# TEMP_HEATER.net
KiCad netlist of a schematic drawn in Altium Designer
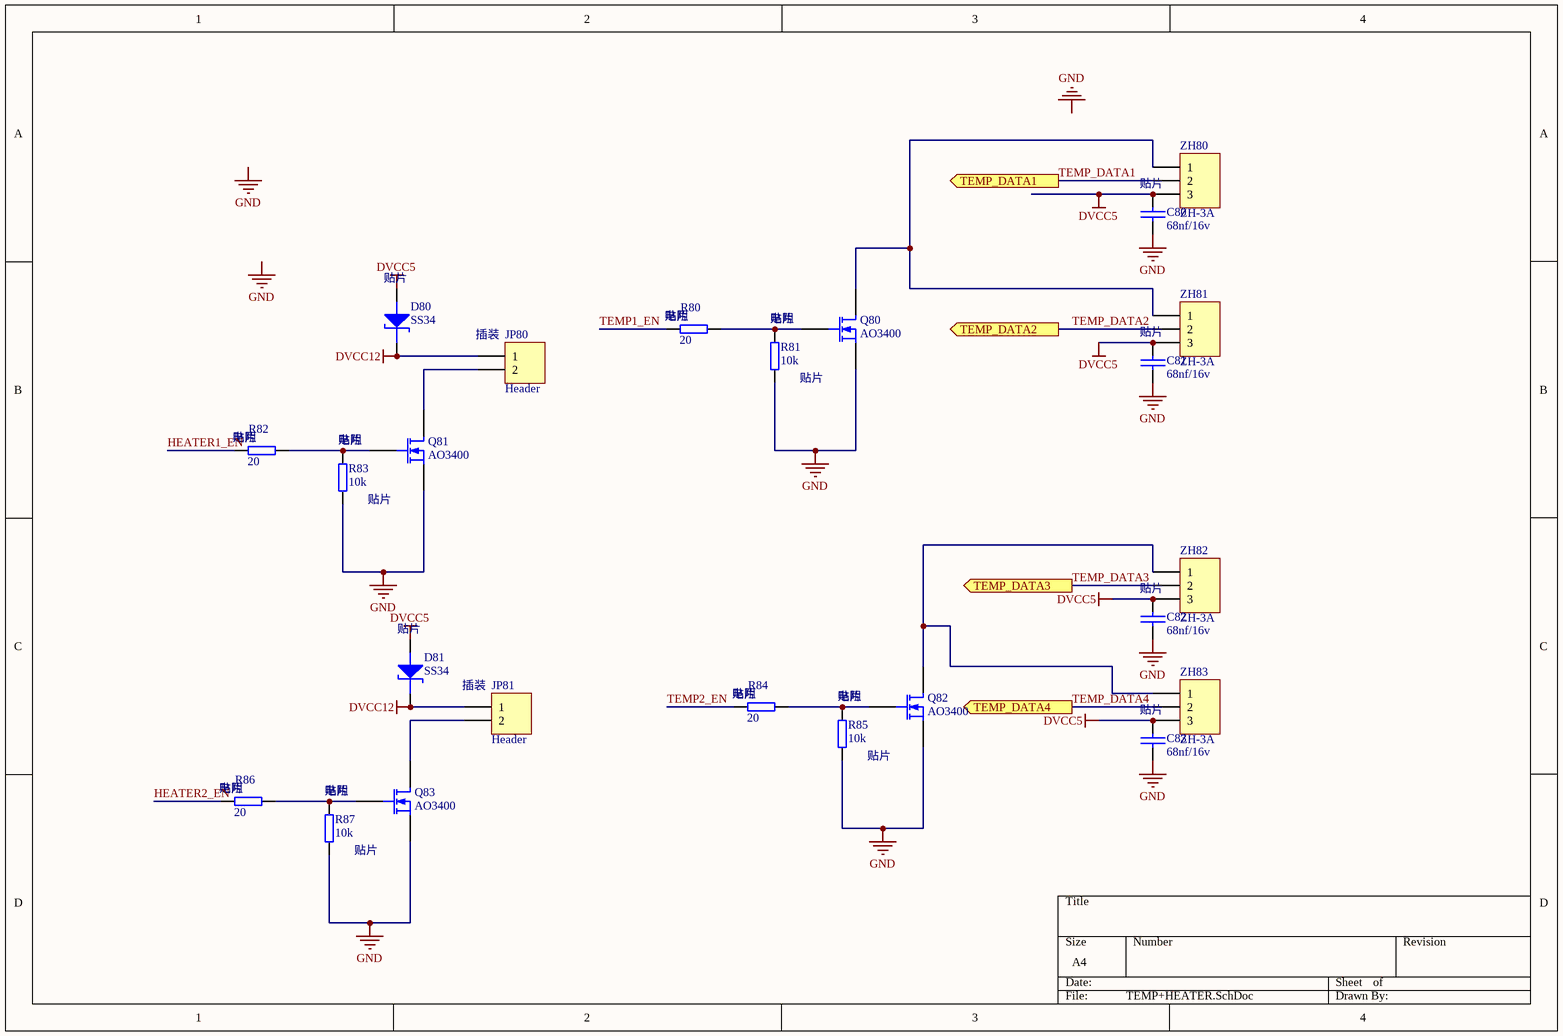
[diagram p0: TEMP+HEATER.SchDoc]

(export (version "E")
  (design (tool "Eeschema 10.0.6"))
  (components
    (comp (ref "C80")
      (value "68nf/16v")
      (footprint "C0402")
      (description "C")
      (libsource (lib "CxyDXP_SCH") (part "CC"))
    )
    (comp (ref "C81")
      (value "68nf/16v")
      (footprint "C0402")
      (description "C")
      (libsource (lib "CxyDXP_SCH") (part "CC"))
    )
    (comp (ref "C82")
      (value "68nf/16v")
      (footprint "C0402")
      (description "C")
      (libsource (lib "CxyDXP_SCH") (part "CC"))
    )
    (comp (ref "C83")
      (value "68nf/16v")
      (footprint "C0402")
      (description "C")
      (libsource (lib "CxyDXP_SCH") (part "CC"))
    )
    (comp (ref "D80") (value "SS34") (footprint "BGY220D") (libsource (lib "CxyDXP_SCH") (part "1N5819")))
    (comp (ref "D81") (value "SS34") (footprint "BGY220D") (libsource (lib "CxyDXP_SCH") (part "1N5819")))
    (comp (ref "JP80")
      (value "Header")
      (footprint "PTC")
      (description "Header, 2-Pin")
      (libsource (lib "Miscellaneous Connectors") (part "Header 2"))
    )
    (comp (ref "JP81")
      (value "Header")
      (footprint "PTC")
      (description "Header, 2-Pin")
      (libsource (lib "Miscellaneous Connectors") (part "Header 2"))
    )
    (comp (ref "Q80")
      (value "AO3400")
      (footprint "SI2300")
      (description "N-Channel MOSFET")
      (libsource (lib "Miscellaneous Devices") (part "MOSFET-N"))
    )
    (comp (ref "Q81")
      (value "AO3400")
      (footprint "SI2300")
      (description "N-Channel MOSFET")
      (libsource (lib "Miscellaneous Devices") (part "MOSFET-N"))
    )
    (comp (ref "Q82")
      (value "AO3400")
      (footprint "SI2300")
      (description "N-Channel MOSFET")
      (libsource (lib "Miscellaneous Devices") (part "MOSFET-N"))
    )
    (comp (ref "Q83")
      (value "AO3400")
      (footprint "SI2300")
      (description "N-Channel MOSFET")
      (libsource (lib "Miscellaneous Devices") (part "MOSFET-N"))
    )
    (comp (ref "R80") (value "20") (footprint "R0402") (libsource (lib "CxyDXP_SCH") (part "RES1")))
    (comp (ref "R81") (value "10k") (footprint "R0402") (libsource (lib "CxyDXP_SCH") (part "RES1")))
    (comp (ref "R82") (value "20") (footprint "R0402") (libsource (lib "CxyDXP_SCH") (part "RES1")))
    (comp (ref "R83") (value "10k") (footprint "R0402") (libsource (lib "CxyDXP_SCH") (part "RES1")))
    (comp (ref "R84") (value "20") (footprint "R0402") (libsource (lib "CxyDXP_SCH") (part "RES1")))
    (comp (ref "R85") (value "10k") (footprint "R0402") (libsource (lib "CxyDXP_SCH") (part "RES1")))
    (comp (ref "R86") (value "20") (footprint "R0402") (libsource (lib "CxyDXP_SCH") (part "RES1")))
    (comp (ref "R87") (value "10k") (footprint "R0402") (libsource (lib "CxyDXP_SCH") (part "RES1")))
    (comp (ref "ZH80")
      (value "ZH-3A")
      (footprint "DS18B20")
      (description "1.5mm")
      (fields (field (name "PUBLISHER") "Altium Limited"))
      (libsource (lib "Connectors") (part "ZH-3A"))
    )
    (comp (ref "ZH81")
      (value "ZH-3A")
      (footprint "DS18B20")
      (description "1.5mm")
      (fields (field (name "PUBLISHER") "Altium Limited"))
      (libsource (lib "Connectors") (part "ZH-3A"))
    )
    (comp (ref "ZH82")
      (value "ZH-3A")
      (footprint "DS18B20")
      (description "1.5mm")
      (fields (field (name "PUBLISHER") "Altium Limited"))
      (libsource (lib "Connectors") (part "ZH-3A"))
    )
    (comp (ref "ZH83")
      (value "ZH-3A")
      (footprint "DS18B20")
      (description "1.5mm")
      (fields (field (name "PUBLISHER") "Altium Limited"))
      (libsource (lib "Connectors") (part "ZH-3A"))
    )
  )
  (nets
    (net (code "1") (name "/HEATER1_EN") (class "Default")
      (node (ref "R82") (pin "2") (pinfunction "2_2") (pintype "passive"))
    )
    (net (code "2") (name "/HEATER2_EN") (class "Default")
      (node (ref "R86") (pin "2") (pinfunction "2_2") (pintype "passive"))
    )
    (net (code "3") (name "/TEMP1_EN") (class "Default")
      (node (ref "R80") (pin "2") (pinfunction "2_2") (pintype "passive"))
    )
    (net (code "4") (name "/TEMP2_EN") (class "Default")
      (node (ref "R84") (pin "2") (pinfunction "2_2") (pintype "passive"))
    )
    (net (code "5") (name "/TEMP_DATA1") (class "Default")
      (node (ref "ZH80") (pin "2") (pinfunction "2_2") (pintype "passive"))
    )
    (net (code "6") (name "/TEMP_DATA2") (class "Default")
      (node (ref "ZH81") (pin "2") (pinfunction "2_2") (pintype "passive"))
    )
    (net (code "7") (name "/TEMP_DATA3") (class "Default")
      (node (ref "ZH82") (pin "2") (pinfunction "2_2") (pintype "passive"))
    )
    (net (code "8") (name "/TEMP_DATA4") (class "Default")
      (node (ref "ZH83") (pin "2") (pinfunction "2_2") (pintype "passive"))
    )
    (net (code "9") (name "DVCC5") (class "Default")
      (node (ref "C80") (pin "2") (pintype "passive"))
      (node (ref "C81") (pin "2") (pintype "passive"))
      (node (ref "C82") (pin "2") (pintype "passive"))
      (node (ref "C83") (pin "2") (pintype "passive"))
      (node (ref "D80") (pin "1") (pinfunction "A_1") (pintype "passive"))
      (node (ref "D81") (pin "1") (pinfunction "A_1") (pintype "passive"))
      (node (ref "ZH80") (pin "3") (pinfunction "3_3") (pintype "passive"))
      (node (ref "ZH81") (pin "3") (pinfunction "3_3") (pintype "passive"))
      (node (ref "ZH82") (pin "3") (pinfunction "3_3") (pintype "passive"))
      (node (ref "ZH83") (pin "3") (pinfunction "3_3") (pintype "passive"))
    )
    (net (code "10") (name "DVCC12") (class "Default")
      (node (ref "D80") (pin "2") (pinfunction "K_2") (pintype "passive"))
      (node (ref "D81") (pin "2") (pinfunction "K_2") (pintype "passive"))
      (node (ref "JP80") (pin "1") (pinfunction "1_1") (pintype "passive"))
      (node (ref "JP81") (pin "1") (pinfunction "1_1") (pintype "passive"))
    )
    (net (code "11") (name "GND") (class "Default")
      (node (ref "C80") (pin "1") (pintype "passive"))
      (node (ref "C81") (pin "1") (pintype "passive"))
      (node (ref "C82") (pin "1") (pintype "passive"))
      (node (ref "C83") (pin "1") (pintype "passive"))
      (node (ref "Q80") (pin "3") (pinfunction "S_3") (pintype "passive"))
      (node (ref "Q81") (pin "3") (pinfunction "S_3") (pintype "passive"))
      (node (ref "Q82") (pin "3") (pinfunction "S_3") (pintype "passive"))
      (node (ref "Q83") (pin "3") (pinfunction "S_3") (pintype "passive"))
      (node (ref "R81") (pin "2") (pinfunction "2_2") (pintype "passive"))
      (node (ref "R83") (pin "2") (pinfunction "2_2") (pintype "passive"))
      (node (ref "R85") (pin "2") (pinfunction "2_2") (pintype "passive"))
      (node (ref "R87") (pin "2") (pinfunction "2_2") (pintype "passive"))
    )
    (net (code "12") (name "Net-(Q80-D)") (class "Default")
      (node (ref "Q80") (pin "1") (pinfunction "D_1") (pintype "passive"))
      (node (ref "ZH80") (pin "1") (pinfunction "1_1") (pintype "passive"))
      (node (ref "ZH81") (pin "1") (pinfunction "1_1") (pintype "passive"))
    )
    (net (code "13") (name "Net-(Q80-G)") (class "Default")
      (node (ref "Q80") (pin "2") (pinfunction "G_2") (pintype "passive"))
      (node (ref "R80") (pin "1") (pinfunction "1_1") (pintype "passive"))
      (node (ref "R81") (pin "1") (pinfunction "1_1") (pintype "passive"))
    )
    (net (code "14") (name "Net-(Q81-D)") (class "Default")
      (node (ref "JP80") (pin "2") (pinfunction "2_2") (pintype "passive"))
      (node (ref "Q81") (pin "1") (pinfunction "D_1") (pintype "passive"))
    )
    (net (code "15") (name "Net-(Q81-G)") (class "Default")
      (node (ref "Q81") (pin "2") (pinfunction "G_2") (pintype "passive"))
      (node (ref "R82") (pin "1") (pinfunction "1_1") (pintype "passive"))
      (node (ref "R83") (pin "1") (pinfunction "1_1") (pintype "passive"))
    )
    (net (code "16") (name "Net-(Q82-D)") (class "Default")
      (node (ref "Q82") (pin "1") (pinfunction "D_1") (pintype "passive"))
      (node (ref "ZH82") (pin "1") (pinfunction "1_1") (pintype "passive"))
      (node (ref "ZH83") (pin "1") (pinfunction "1_1") (pintype "passive"))
    )
    (net (code "17") (name "Net-(Q82-G)") (class "Default")
      (node (ref "Q82") (pin "2") (pinfunction "G_2") (pintype "passive"))
      (node (ref "R84") (pin "1") (pinfunction "1_1") (pintype "passive"))
      (node (ref "R85") (pin "1") (pinfunction "1_1") (pintype "passive"))
    )
    (net (code "18") (name "Net-(Q83-D)") (class "Default")
      (node (ref "JP81") (pin "2") (pinfunction "2_2") (pintype "passive"))
      (node (ref "Q83") (pin "1") (pinfunction "D_1") (pintype "passive"))
    )
    (net (code "19") (name "Net-(Q83-G)") (class "Default")
      (node (ref "Q83") (pin "2") (pinfunction "G_2") (pintype "passive"))
      (node (ref "R86") (pin "1") (pinfunction "1_1") (pintype "passive"))
      (node (ref "R87") (pin "1") (pinfunction "1_1") (pintype "passive"))
    )
  )
)
